# PH.net
KiCad netlist of a schematic drawn in Altium Designer
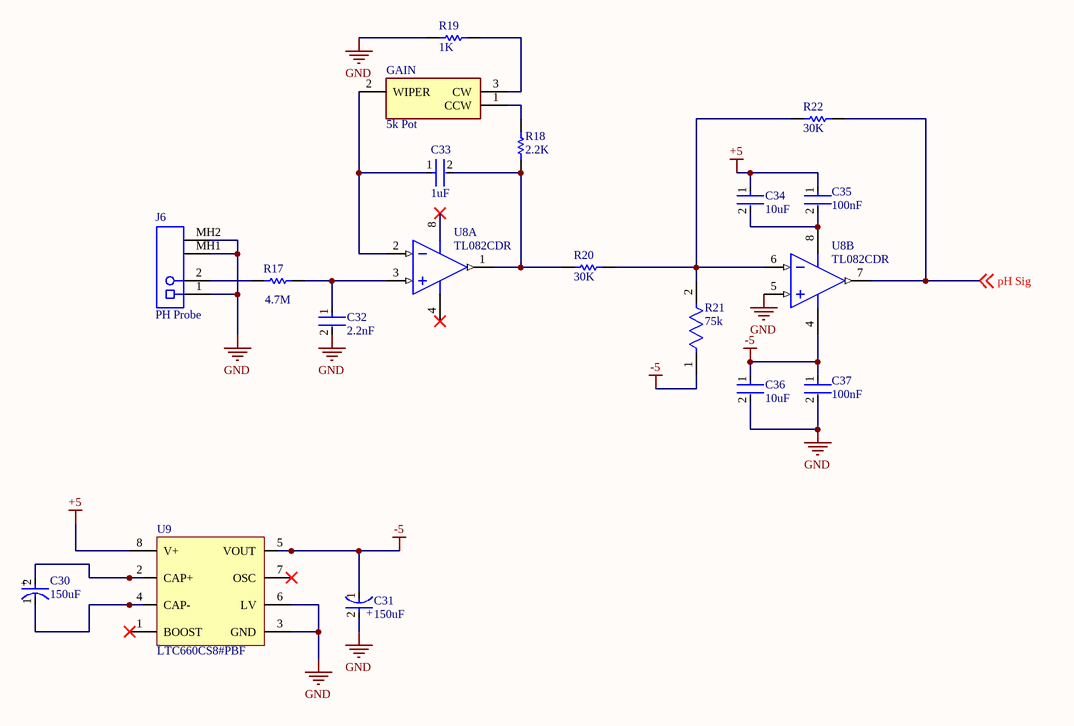
[diagram p0: PH.SchDoc]

(export (version "E")
  (design (tool "Eeschema 10.0.6"))
  (components
    (comp (ref "C30")
      (value "150uF")
      (footprint "FP-POSCAP-D3L-MFG")
      (description "Molded Tantalum Polymer Capacitor 150uF 20% 10V life 2000Hours SMD 2917")
      (fields (field (name "TOLERANCE") "20%") (field (name "VOLTAGE") "10V"))
      (libsource (lib "Altium Content Vault") (part "a00bbbee19879c290e62620ae7e47b1"))
    )
    (comp (ref "C31")
      (value "150uF")
      (footprint "FP-POSCAP-D3L-MFG")
      (description "Molded Tantalum Polymer Capacitor 150uF 20% 10V life 2000Hours SMD 2917")
      (fields (field (name "TOLERANCE") "20%") (field (name "VOLTAGE") "10V"))
      (libsource (lib "Altium Content Vault") (part "a00bbbee19879c290e62620ae7e47b1"))
    )
    (comp (ref "C32")
      (value "2.2nF")
      (footprint "FP-GRM188-0_1-e0_2_0_5-MFG")
      (description "Chip Multilayer Ceramic Capacitors for General Purpose, 0603, 2200pF, C0G, 30ppm/°C, 5%, 50V")
      (fields (field (name "VOLTAGE") "50V") (field (name "TOLERANCE") "5%"))
      (libsource (lib "Altium Content Vault") (part "11868f565c42a9108669ba33697ecf6"))
    )
    (comp (ref "C33")
      (value "1uF")
      (footprint "FP-0603-L_1_6_0_1-W_0_8_0-IPC_A")
      (description "None")
      (fields (field (name "TOLERANCE") "10%"))
      (libsource (lib "Altium Content Vault") (part "02cd4be3c70576c341d710602a673aa"))
    )
    (comp (ref "C34")
      (value "10uF")
      (footprint "FP-C0805C-DG-MFG")
      (description "CAP CER 10UF 10V X5R 0805")
      (fields (field (name "TOLERANCE") "10%") (field (name "MANUFACTURER PART NUMBER") "C0805C106K8PACTU"))
      (libsource (lib "Altium Content Vault") (part "11868f565c42a9108669ba33697ecf6"))
    )
    (comp (ref "C35")
      (value "100nF")
      (footprint "FP-CGA3E-0_3-0_1-IPC_A")
      (description "Cap Ceramic 100nF 50V X7R 10% Pad SMD 0603 +125°C Automotive T/R")
      (fields (field (name "TOLERANCE") "10%") (field (name "VOLTAGE") "50V"))
      (libsource (lib "Altium Content Vault") (part "b4654b650e69147ec39a6b967a45e02"))
    )
    (comp (ref "C36")
      (value "10uF")
      (footprint "FP-C0805C-DG-MFG")
      (description "CAP CER 10UF 10V X5R 0805")
      (fields (field (name "TOLERANCE") "10%") (field (name "MANUFACTURER PART NUMBER") "C0805C106K8PACTU"))
      (libsource (lib "Altium Content Vault") (part "11868f565c42a9108669ba33697ecf6"))
    )
    (comp (ref "C37")
      (value "100nF")
      (footprint "FP-CGA3E-0_3-0_1-IPC_A")
      (description "Cap Ceramic 100nF 50V X7R 10% Pad SMD 0603 +125°C Automotive T/R")
      (fields (field (name "TOLERANCE") "10%") (field (name "VOLTAGE") "50V"))
      (libsource (lib "Altium Content Vault") (part "b4654b650e69147ec39a6b967a45e02"))
    )
    (comp (ref "GAIN")
      (value "5k Pot")
      (footprint "SamacSys:3296Y1502LF")
      (description "Variable Resistor")
      (fields
        (field (name "MANUFACTURER_PART_NUMBER") "3296Y-1-502LF")
        (field (name "MOUSER PART NUMBER") "652-3296Y-1-502LF")
      )
      (libsource (lib "*") (part "3296Y-1-502LF"))
    )
    (comp (ref "J6")
      (value "PH Probe")
      (footprint "TECO-1-1337543-0_V")
      (fields (field (name "MANUFACTURER") "TE Connectivity"))
      (libsource (lib "Altium Content Vault") (part "CN-1P-F-R2_A"))
    )
    (comp (ref "R17")
      (value "4.7M")
      (footprint "RESC1609X50X30LL10T20")
      (fields (field (name "MANUFACTURER") "Vishay Dale") (field (name "PART NUMBER") "CRCW06034M70FKEA"))
      (libsource (lib "Altium Content Vault") (part "RES"))
    )
    (comp (ref "R18")
      (value "2.2K")
      (footprint "RESC1608X55X30ML20T20")
      (fields (field (name "MANUFACTURER") "Panasonic") (field (name "PART NUMBER") "ERA3AEB222V"))
      (libsource (lib "Altium Content Vault") (part "RES"))
    )
    (comp (ref "R19")
      (value "1K")
      (footprint "RESC2013X50X30NL20T20")
      (fields (field (name "PART NUMBER") "CRCW08051K00FKEA") (field (name "MANUFACTURER") "Vishay Dale"))
      (libsource (lib "Altium Content Vault") (part "RES"))
    )
    (comp (ref "R20")
      (value "30K")
      (footprint "RESC1609X50X30LL10T20")
      (fields (field (name "PART NUMBER") "CRCW060330K0FKEA") (field (name "MANUFACTURER") "Vishay Dale"))
      (libsource (lib "Altium Content Vault") (part "RES"))
    )
    (comp (ref "R21")
      (value "75k")
      (footprint "FP-ERA3A-MFG")
      (description "RES SMD 75K OHM 0.1% 1/10W 0603")
      (fields
        (field (name "MANUFACTURER") "Panasonic")
        (field (name "OCTOPART") "https://octopart.com/era-3aeb753v-panasonic-1225046")
      )
      (libsource (lib "Altium Content Vault") (part "1029c3af85768c4190bb7ad29bc67b5"))
    )
    (comp (ref "R22")
      (value "30K")
      (footprint "RESC1609X50X30LL10T20")
      (fields (field (name "PART NUMBER") "CRCW060330K0FKEA") (field (name "MANUFACTURER") "Vishay Dale"))
      (libsource (lib "Altium Content Vault") (part "RES"))
    )
    (comp (ref "U8")
      (value "TL082CDR")
      (footprint "D0008A_N")
      (fields (field (name "MANUFACTURER") "Texas Instruments"))
      (libsource (lib "Altium Content Vault") (part "TI-AMP-D6-2-8_D"))
    )
    (comp (ref "U9")
      (value "LTC660CS8#PBF")
      (footprint "LT-S8-8_L")
      (description "100 mA CMOS Voltage Converter, 1.5 to 5.5 V Vin, 8-pin SOIC (S8-8), 0 to 70 degC, Pb-Free")
      (fields (field (name "MANUFACTURER") "Linear Technology"))
      (libsource (lib "Altium Content Vault") (part "LT-LTC660-8"))
    )
  )
  (nets
    (net (code "1") (name "+5") (class "Default")
      (node (ref "C34") (pin "1") (pinfunction "1_1") (pintype "passive"))
      (node (ref "C35") (pin "1") (pinfunction "1_1") (pintype "passive"))
      (node (ref "U9") (pin "8") (pinfunction "V+_8") (pintype "power_in"))
    )
    (net (code "2") (name "-5") (class "Default")
      (node (ref "C31") (pin "1") (pinfunction "C_1") (pintype "passive"))
      (node (ref "C36") (pin "1") (pinfunction "1_1") (pintype "passive"))
      (node (ref "C37") (pin "1") (pinfunction "1_1") (pintype "passive"))
      (node (ref "R21") (pin "1") (pinfunction "1_1") (pintype "passive"))
      (node (ref "U8") (pin "4") (pinfunction "VCC-_4") (pintype "power_in"))
      (node (ref "U9") (pin "5") (pinfunction "VOUT_5") (pintype "power_in"))
    )
    (net (code "3") (name "GND") (class "Default")
      (node (ref "C31") (pin "2") (pinfunction "A_2") (pintype "passive"))
      (node (ref "C32") (pin "2") (pinfunction "2_2") (pintype "passive"))
      (node (ref "C36") (pin "2") (pinfunction "2_2") (pintype "passive"))
      (node (ref "C37") (pin "2") (pinfunction "2_2") (pintype "passive"))
      (node (ref "J6") (pin "1") (pinfunction "1_1") (pintype "passive"))
      (node (ref "J6") (pin "MH1") (pinfunction "MH1_MH1") (pintype "passive"))
      (node (ref "J6") (pin "MH2") (pinfunction "MH2_MH2") (pintype "passive"))
      (node (ref "R19") (pin "2") (pinfunction "2_2") (pintype "passive"))
      (node (ref "U8") (pin "5") (pinfunction "IN2+_5") (pintype "input"))
      (node (ref "U9") (pin "3") (pinfunction "GND_3") (pintype "power_in"))
      (node (ref "U9") (pin "6") (pinfunction "LV_6") (pintype "passive"))
    )
    (net (code "4") (name "Net-(C30-A)") (class "Default")
      (node (ref "C30") (pin "2") (pinfunction "A_2") (pintype "passive"))
      (node (ref "U9") (pin "2") (pinfunction "CAP+_2") (pintype "passive"))
    )
    (net (code "5") (name "Net-(C30-C)") (class "Default")
      (node (ref "C30") (pin "1") (pinfunction "C_1") (pintype "passive"))
      (node (ref "U9") (pin "4") (pinfunction "CAP-_4") (pintype "passive"))
    )
    (net (code "6") (name "Net-(GAIN-CCW)") (class "Default")
      (node (ref "GAIN") (pin "1") (pinfunction "CCW_1") (pintype "passive"))
      (node (ref "R18") (pin "2") (pinfunction "2_2") (pintype "passive"))
    )
    (net (code "7") (name "Net-(GAIN-CW)") (class "Default")
      (node (ref "GAIN") (pin "3") (pinfunction "CW_3") (pintype "passive"))
      (node (ref "R19") (pin "1") (pinfunction "1_1") (pintype "passive"))
    )
    (net (code "8") (name "Net-(GAIN-WIPER)") (class "Default")
      (node (ref "C33") (pin "1") (pinfunction "1_1") (pintype "passive"))
      (node (ref "GAIN") (pin "2") (pinfunction "WIPER_2") (pintype "passive"))
      (node (ref "U8") (pin "2") (pinfunction "IN1-_2") (pintype "input"))
    )
    (net (code "9") (name "Net-(J6-Pad2)") (class "Default")
      (node (ref "J6") (pin "2") (pinfunction "2_2") (pintype "passive"))
      (node (ref "R17") (pin "1") (pinfunction "1_1") (pintype "passive"))
    )
    (net (code "10") (name "Net-(U8A-IN1+)") (class "Default")
      (node (ref "C32") (pin "1") (pinfunction "1_1") (pintype "passive"))
      (node (ref "R17") (pin "2") (pinfunction "2_2") (pintype "passive"))
      (node (ref "U8") (pin "3") (pinfunction "IN1+_3") (pintype "input"))
    )
    (net (code "11") (name "Net-(U8A-OUT1)") (class "Default")
      (node (ref "C33") (pin "2") (pinfunction "2_2") (pintype "passive"))
      (node (ref "R18") (pin "1") (pinfunction "1_1") (pintype "passive"))
      (node (ref "R20") (pin "1") (pinfunction "1_1") (pintype "passive"))
      (node (ref "U8") (pin "1") (pinfunction "OUT1_1") (pintype "output"))
    )
    (net (code "12") (name "Net-(U8B-IN2-)") (class "Default")
      (node (ref "R20") (pin "2") (pinfunction "2_2") (pintype "passive"))
      (node (ref "R21") (pin "2") (pinfunction "2_2") (pintype "passive"))
      (node (ref "R22") (pin "1") (pinfunction "1_1") (pintype "passive"))
      (node (ref "U8") (pin "6") (pinfunction "IN2-_6") (pintype "input"))
    )
    (net (code "13") (name "Net-(U8B-VCC+)") (class "Default")
      (node (ref "C34") (pin "2") (pinfunction "2_2") (pintype "passive"))
      (node (ref "C35") (pin "2") (pinfunction "2_2") (pintype "passive"))
      (node (ref "U8") (pin "8") (pinfunction "VCC+_8") (pintype "power_in"))
    )
    (net (code "14") (name "pH Sig") (class "Default")
      (node (ref "R22") (pin "2") (pinfunction "2_2") (pintype "passive"))
      (node (ref "U8") (pin "7") (pinfunction "OUT2_7") (pintype "output"))
    )
    (net (code "15") (name "unconnected-(U8A-VCC+-Pad8)") (class "Default")
      (node (ref "U8") (pin "8") (pinfunction "VCC+_8") (pintype "power_in+no_connect"))
    )
    (net (code "16") (name "unconnected-(U8A-VCC--Pad4)") (class "Default")
      (node (ref "U8") (pin "4") (pinfunction "VCC-_4") (pintype "power_in+no_connect"))
    )
    (net (code "17") (name "unconnected-(U9-BOOST-Pad1)") (class "Default")
      (node (ref "U9") (pin "1") (pinfunction "BOOST_1") (pintype "passive+no_connect"))
    )
    (net (code "18") (name "unconnected-(U9-OSC-Pad7)") (class "Default")
      (node (ref "U9") (pin "7") (pinfunction "OSC_7") (pintype "passive+no_connect"))
    )
  )
)
